# programmeShematics.net
KiCad netlist of a schematic drawn in Altium Designer
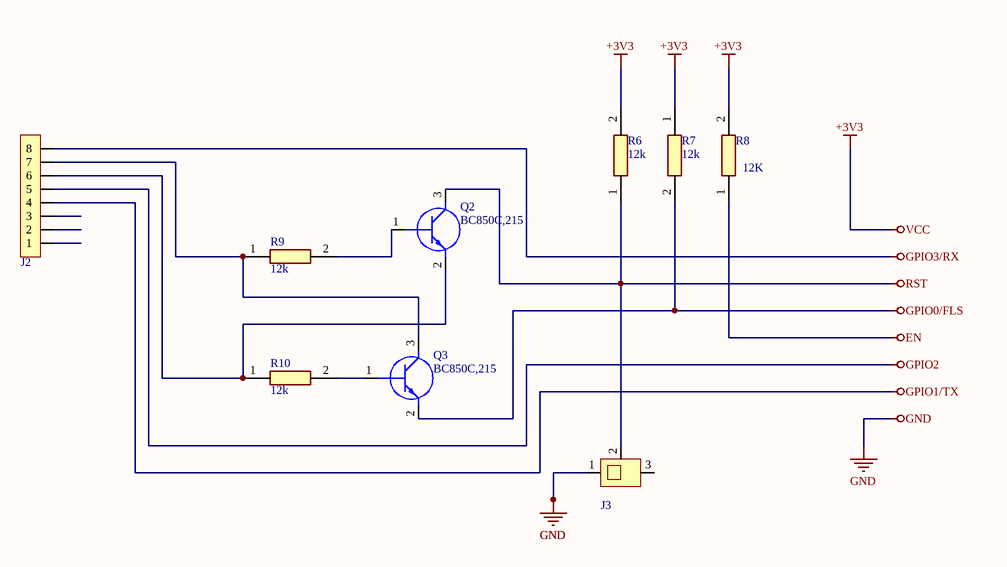
[diagram p0: programmeShematics.SchDoc]

(export (version "E")
  (design (tool "Eeschema 10.0.6"))
  (components
    (comp (ref "J2")
      (value "Header Pins")
      (footprint "HEADER PIN 1x8")
      (libsource (lib "ACR Components") (part "Header Pins 1x8"))
    )
    (comp (ref "J3")
      (value "/ss-12d02-vg4")
      (footprint "Switch button")
      (libsource (lib "ACR Components") (part "Switch slide button"))
    )
    (comp (ref "Q2")
      (value "BC850C,215")
      (footprint "SOT23")
      (description "Transistor BJT NPN")
      (fields (field (name "MOUSER PART NUMBER") "771-BC850C-T/R"))
      (libsource (lib "*") (part "BC850C,215"))
    )
    (comp (ref "Q3")
      (value "BC850C,215")
      (footprint "SOT23")
      (description "Transistor BJT NPN")
      (fields (field (name "MOUSER PART NUMBER") "771-BC850C-T/R"))
      (libsource (lib "SamacSys") (part "BC850C,215"))
    )
    (comp (ref "R6")
      (value "12k")
      (footprint "SamacSys:RESC2012X65N")
      (description "Resistor")
      (fields (field (name "MANUFACTURER_PART_NUMBER") "CPF0805B102RE1"))
      (libsource (lib "") (part "CPF0805B102RE1_1"))
    )
    (comp (ref "R7")
      (value "12k")
      (footprint "SamacSys:RESC2012X65N")
      (description "Resistor")
      (fields (field (name "MANUFACTURER_PART_NUMBER") "CPF0805B102RE1"))
      (libsource (lib "SamacSys") (part "CPF0805B102RE1"))
    )
    (comp (ref "R8")
      (value "12K")
      (footprint "SamacSys:RESC2012X65N")
      (description "Resistor")
      (fields (field (name "MANUFACTURER_PART_NUMBER") "CPF0805B102RE1"))
      (libsource (lib "") (part "CPF0805B102RE1_1"))
    )
    (comp (ref "R9")
      (value "12k")
      (footprint "SamacSys:RESC2012X65N")
      (description "Resistor")
      (fields (field (name "MANUFACTURER_PART_NUMBER") "CPF0805B102RE1"))
      (libsource (lib "") (part "CPF0805B102RE1_2"))
    )
    (comp (ref "R10")
      (value "12k")
      (footprint "SamacSys:RESC2012X65N")
      (description "Resistor")
      (fields (field (name "MANUFACTURER_PART_NUMBER") "CPF0805B102RE1"))
      (libsource (lib "") (part "CPF0805B102RE1_2"))
    )
  )
  (nets
    (net (code "1") (name "+3V3") (class "Default")
      (node (ref "R6") (pin "2") (pinfunction "2_2") (pintype "passive"))
      (node (ref "R7") (pin "1") (pinfunction "1_1") (pintype "passive"))
      (node (ref "R8") (pin "2") (pinfunction "2_2") (pintype "passive"))
    )
    (net (code "2") (name "EN") (class "Default")
      (node (ref "R8") (pin "1") (pinfunction "1_1") (pintype "passive"))
    )
    (net (code "3") (name "GND") (class "Default")
      (node (ref "J3") (pin "1") (pinfunction "1_1") (pintype "passive"))
    )
    (net (code "4") (name "GPIO0{slash}FLS") (class "Default")
      (node (ref "Q3") (pin "2") (pinfunction "E_2") (pintype "passive"))
      (node (ref "R7") (pin "2") (pinfunction "2_2") (pintype "passive"))
    )
    (net (code "5") (name "GPIO1{slash}TX") (class "Default")
      (node (ref "J2") (pin "4") (pinfunction "4_4") (pintype "passive"))
    )
    (net (code "6") (name "GPIO2") (class "Default")
      (node (ref "J2") (pin "5") (pinfunction "5_5") (pintype "passive"))
    )
    (net (code "7") (name "GPIO3{slash}RX") (class "Default")
      (node (ref "J2") (pin "8") (pinfunction "8_8") (pintype "passive"))
    )
    (net (code "8") (name "Net-(Q2-B)") (class "Default")
      (node (ref "Q2") (pin "1") (pinfunction "B_1") (pintype "passive"))
      (node (ref "R9") (pin "2") (pinfunction "2_2") (pintype "passive"))
    )
    (net (code "9") (name "Net-(Q2-E)") (class "Default")
      (node (ref "J2") (pin "6") (pinfunction "6_6") (pintype "passive"))
      (node (ref "Q2") (pin "2") (pinfunction "E_2") (pintype "passive"))
      (node (ref "R10") (pin "1") (pinfunction "1_1") (pintype "passive"))
    )
    (net (code "10") (name "Net-(Q3-B)") (class "Default")
      (node (ref "Q3") (pin "1") (pinfunction "B_1") (pintype "passive"))
      (node (ref "R10") (pin "2") (pinfunction "2_2") (pintype "passive"))
    )
    (net (code "11") (name "Net-(Q3-C)") (class "Default")
      (node (ref "J2") (pin "7") (pinfunction "7_7") (pintype "passive"))
      (node (ref "Q3") (pin "3") (pinfunction "C_3") (pintype "passive"))
      (node (ref "R9") (pin "1") (pinfunction "1_1") (pintype "passive"))
    )
    (net (code "12") (name "RST") (class "Default")
      (node (ref "J3") (pin "2") (pinfunction "2_2") (pintype "passive"))
      (node (ref "Q2") (pin "3") (pinfunction "C_3") (pintype "passive"))
      (node (ref "R6") (pin "1") (pinfunction "1_1") (pintype "passive"))
    )
    (net (code "13") (name "unconnected-(J2-Pad1)") (class "Default")
      (node (ref "J2") (pin "1") (pinfunction "1_1") (pintype "passive"))
    )
    (net (code "14") (name "unconnected-(J2-Pad2)") (class "Default")
      (node (ref "J2") (pin "2") (pinfunction "2_2") (pintype "passive"))
    )
    (net (code "15") (name "unconnected-(J2-Pad3)") (class "Default")
      (node (ref "J2") (pin "3") (pinfunction "3_3") (pintype "passive"))
    )
    (net (code "16") (name "unconnected-(J3-Pad3)") (class "Default")
      (node (ref "J3") (pin "3") (pinfunction "3_3") (pintype "passive"))
    )
  )
)
